# Power.net
KiCad netlist of a schematic drawn in Altium Designer
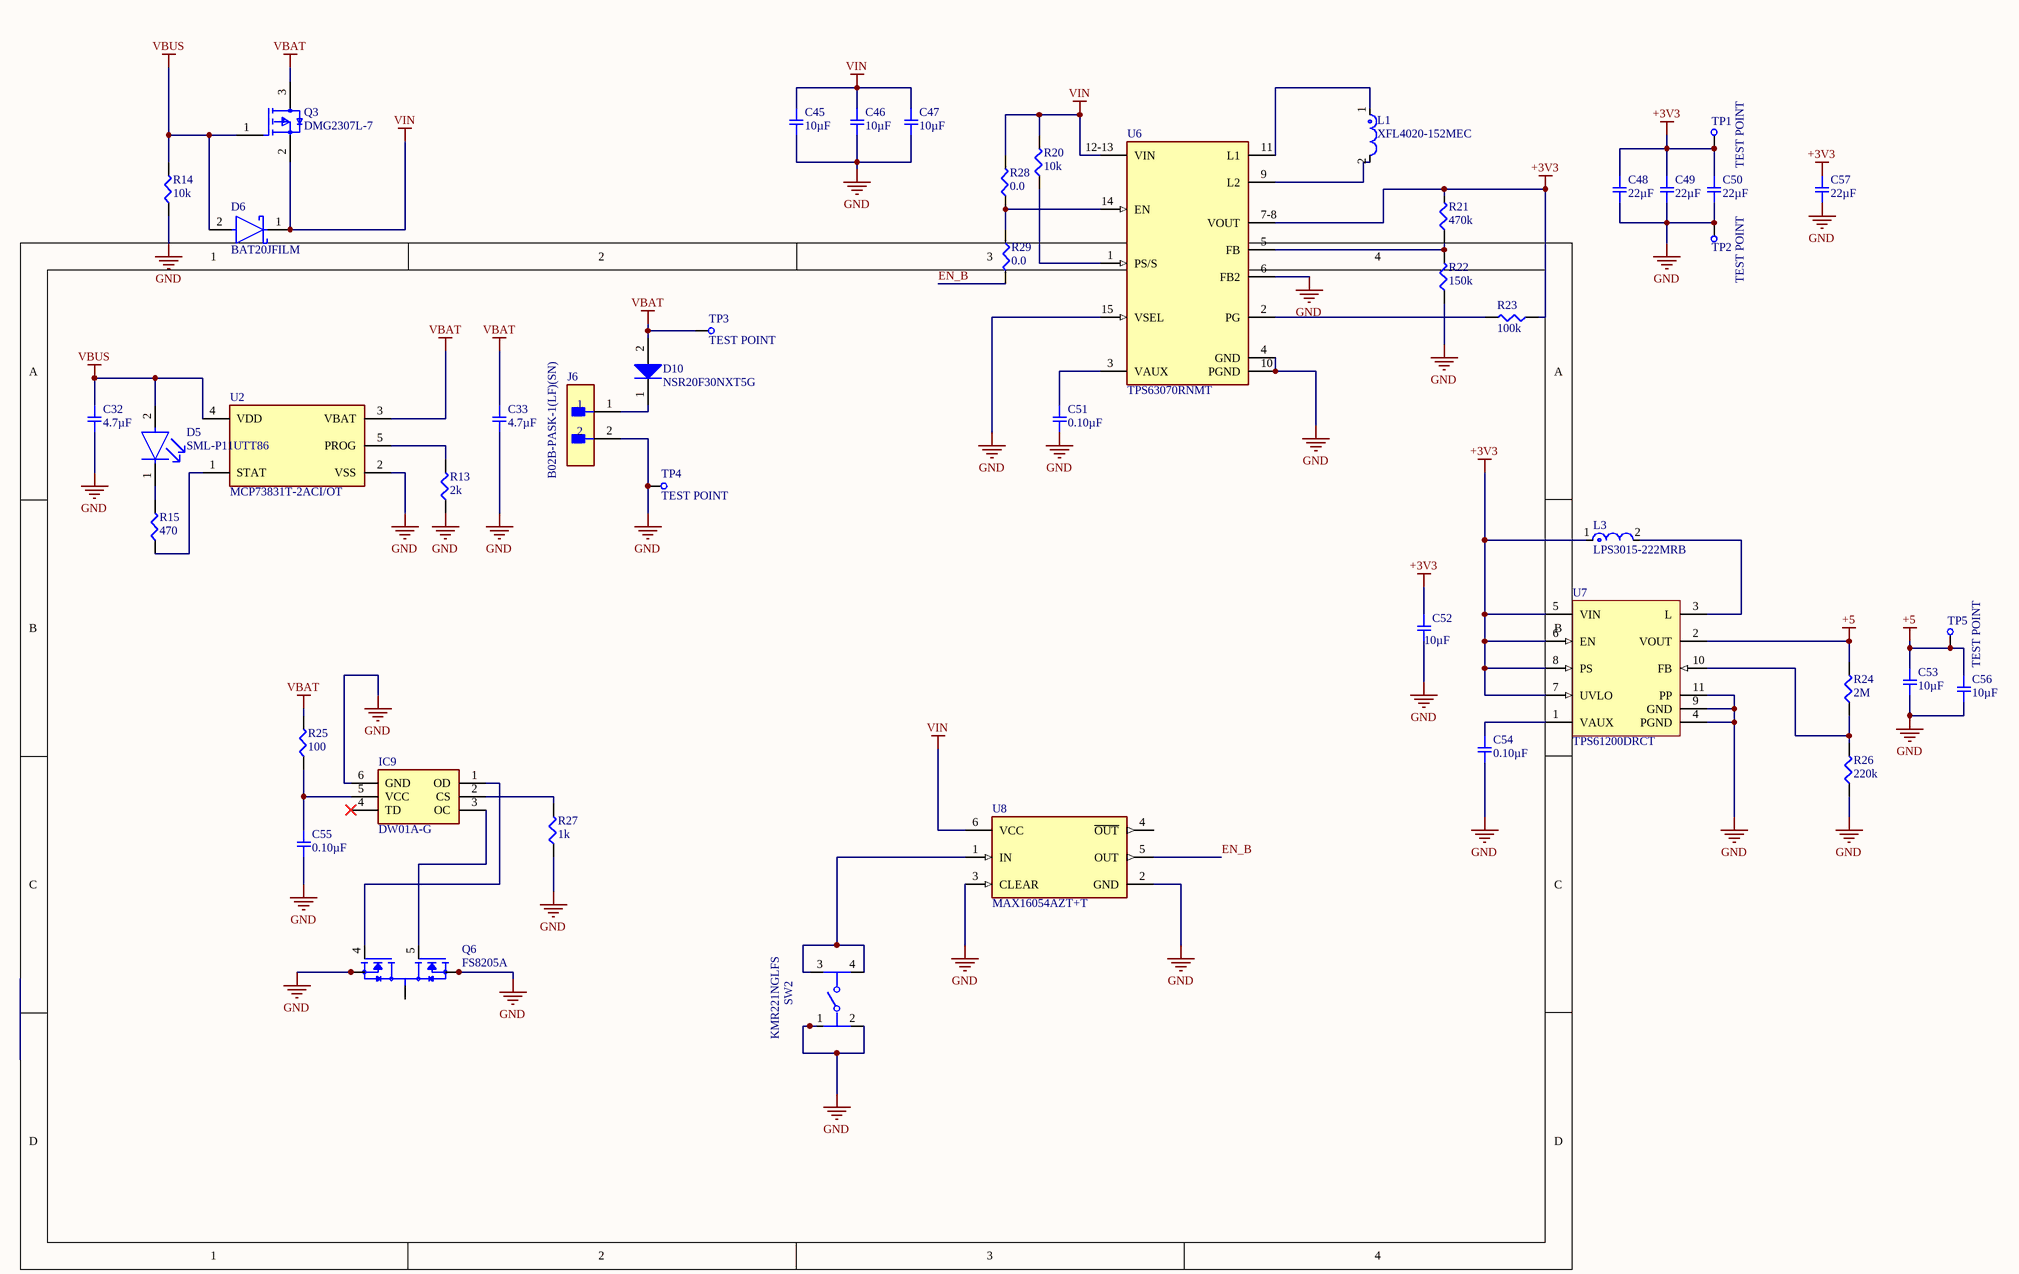
[diagram p0: Power.SchDoc]

(export (version "E")
  (design (tool "Eeschema 10.0.6"))
  (components
    (comp (ref "C32")
      (value "4.7µF")
      (footprint "SMD-0402C")
      (description "CAP CER 4.7UF 10V X5R 0402")
      (fields
        (field (name "DIGI-KEY PART NUMBER") "490-13252-1-ND")
        (field (name "PART NUMBER") "ZRB15XR61A475KE01D")
      )
      (libsource (lib "capacitor_murata_0402") (part "ZRB15XR61A475KE01D"))
    )
    (comp (ref "C33")
      (value "4.7µF")
      (footprint "SMD-0402C")
      (description "CAP CER 4.7UF 10V X5R 0402")
      (fields
        (field (name "DIGI-KEY PART NUMBER") "490-13252-1-ND")
        (field (name "PART NUMBER") "ZRB15XR61A475KE01D")
      )
      (libsource (lib "capacitor_murata_0402") (part "ZRB15XR61A475KE01D"))
    )
    (comp (ref "C45")
      (value "10µF")
      (footprint "SMD-0805C")
      (description "CAP CER 10UF 10V X7R 0805")
      (fields
        (field (name "DIGI-KEY PART NUMBER") "490-12646-1-ND")
        (field (name "PART NUMBER") "GCJ21BR71A106KE01L")
      )
      (libsource (lib "capacitor_murata_0805") (part "GCJ21BR71A106KE01L"))
    )
    (comp (ref "C46")
      (value "10µF")
      (footprint "SMD-0805C")
      (description "CAP CER 10UF 10V X7R 0805")
      (fields
        (field (name "DIGI-KEY PART NUMBER") "490-12646-1-ND")
        (field (name "PART NUMBER") "GCJ21BR71A106KE01L")
      )
      (libsource (lib "capacitor_murata_0805") (part "GCJ21BR71A106KE01L"))
    )
    (comp (ref "C47")
      (value "10µF")
      (footprint "SMD-0603C")
      (description "CAP CER 10UF 16V X6S 0603")
      (fields
        (field (name "DIGI-KEY PART NUMBER") "490-7198-1-ND")
        (field (name "PART NUMBER") "GRM188C81C106MA73D")
      )
      (libsource (lib "capacitor_murata_0603") (part "GRM188C81C106MA73D"))
    )
    (comp (ref "C48")
      (value "22µF")
      (footprint "SMD-0805C")
      (description "CAP CER 22UF 10V X5R 0805")
      (fields
        (field (name "DIGI-KEY PART NUMBER") "490-9951-1-ND")
        (field (name "PART NUMBER") "GRM219R61A226MEA0D")
      )
      (libsource (lib "capacitor_murata_0805") (part "GRM219R61A226MEA0D"))
    )
    (comp (ref "C49")
      (value "22µF")
      (footprint "SMD-0805C")
      (description "CAP CER 22UF 10V X5R 0805")
      (fields
        (field (name "DIGI-KEY PART NUMBER") "490-9951-1-ND")
        (field (name "PART NUMBER") "GRM219R61A226MEA0D")
      )
      (libsource (lib "capacitor_murata_0805") (part "GRM219R61A226MEA0D"))
    )
    (comp (ref "C50")
      (value "22µF")
      (footprint "SMD-0805C")
      (description "CAP CER 22UF 10V X5R 0805")
      (fields
        (field (name "DIGI-KEY PART NUMBER") "490-9951-1-ND")
        (field (name "PART NUMBER") "GRM219R61A226MEA0D")
      )
      (libsource (lib "capacitor_murata_0805") (part "GRM219R61A226MEA0D"))
    )
    (comp (ref "C51")
      (value "0.10µF")
      (footprint "SMD-0402C")
      (description "CAP CER 0.1UF 16V X7R 0402")
      (fields
        (field (name "DIGI-KEY PART NUMBER") "490-4759-1-ND")
        (field (name "PART NUMBER") "GCM155R71C104KA55D")
      )
      (libsource (lib "capacitor_murata_0402") (part "GCM155R71C104KA55D"))
    )
    (comp (ref "C52")
      (value "10µF")
      (footprint "SMD-0603C")
      (description "CAP CER 10UF 16V X5R 0603")
      (fields
        (field (name "DIGI-KEY PART NUMBER") "490-10729-1-ND")
        (field (name "PART NUMBER") "GRM188R61C106MAALD")
      )
      (libsource (lib "capacitor_murata_0603") (part "GRM188R61C106MAALD"))
    )
    (comp (ref "C53")
      (value "10µF")
      (footprint "SMD-0603C")
      (description "CAP CER 10UF 16V X5R 0603")
      (fields
        (field (name "DIGI-KEY PART NUMBER") "490-10729-1-ND")
        (field (name "PART NUMBER") "GRM188R61C106MAALD")
      )
      (libsource (lib "capacitor_murata_0603") (part "GRM188R61C106MAALD"))
    )
    (comp (ref "C54")
      (value "0.10µF")
      (footprint "SMD-0402C")
      (description "CAP CER 0.1UF 16V X7R 0402")
      (fields
        (field (name "DIGI-KEY PART NUMBER") "490-4759-1-ND")
        (field (name "PART NUMBER") "GCM155R71C104KA55D")
      )
      (libsource (lib "capacitor_murata_0402") (part "GCM155R71C104KA55D"))
    )
    (comp (ref "C55")
      (value "0.10µF")
      (footprint "SMD-0402C")
      (description "CAP CER 0.1UF 16V X7R 0402")
      (fields
        (field (name "DIGI-KEY PART NUMBER") "490-4759-1-ND")
        (field (name "PART NUMBER") "GCM155R71C104KA55D")
      )
      (libsource (lib "capacitor_murata_0402") (part "GCM155R71C104KA55D"))
    )
    (comp (ref "C56")
      (value "10µF")
      (footprint "SMD-0603C")
      (description "CAP CER 10UF 16V X5R 0603")
      (fields
        (field (name "DIGI-KEY PART NUMBER") "490-10729-1-ND")
        (field (name "PART NUMBER") "GRM188R61C106MAALD")
      )
      (libsource (lib "capacitor_murata_0603") (part "GRM188R61C106MAALD"))
    )
    (comp (ref "C57")
      (value "22µF")
      (footprint "SMD-0603C")
      (description "CAP CER 22UF 10V X5R 0603")
      (fields
        (field (name "DIGI-KEY PART NUMBER") "490-13243-1-ND")
        (field (name "PART NUMBER") "GRM187R61A226ME15D")
      )
      (libsource (lib "capacitor_murata_0603") (part "GRM187R61A226ME15D"))
    )
    (comp (ref "D5")
      (value "SML-P11UTT86")
      (footprint "FP-SML-P11UTT86-MFG")
      (description "LED RED CLEAR 1006 SMD")
      (libsource (lib "Altium Content Vault") (part "8706943c75ba83719d021d2fdc84c58"))
    )
    (comp (ref "D6")
      (value "BAT20JFILM")
      (footprint "FP-BAT20JFILM-MFG")
      (description "DIODE SCHOTTKY 23V 1A SOD323")
      (libsource (lib "Altium Content Vault") (part "fefb30dabb5d097ae2f038500735429"))
    )
    (comp (ref "D10")
      (value "NSR20F30NXT5G")
      (footprint "ONSC-DSN-2-512AB-01_V")
      (description "Schottky Barrier Diode, 2-Pin DSN, Pb-Free, Tape and Reel")
      (fields (field (name "MANUFACTURER") "On Semiconductor"))
      (libsource (lib "Altium Content Vault") (part "ONSC-D-K1A2-2"))
    )
    (comp (ref "IC9")
      (value "DW01A-G")
      (footprint "SamacSys:SOT95P190X145-6N")
      (description "Integrated Circuit")
      (libsource (lib "*") (part "DW01A-G"))
    )
    (comp (ref "J6")
      (value "B02B-PASK-1(LF)(SN)")
      (footprint "FP-B02B-PASK-1_LF_SN-MFG")
      (description "CONN HEADER VERT 2POS 2MM")
      (libsource (lib "Altium Content Vault") (part "3bc925449376181038e59eaffc5286c"))
    )
    (comp (ref "L1")
      (value "XFL4020-152MEC")
      (footprint "FP-XFL4020-MFG")
      (fields (field (name "TOLERANCE") "20%"))
      (libsource (lib "Altium Content Vault") (part "4cc4b267dca4c8e51f7102f422741d8"))
    )
    (comp (ref "L3")
      (value "LPS3015-222MRB")
      (footprint "FP-LPS3015-MFG")
      (description "Fixed Inductors LPS3015 AEC-Q200 2.2uH 1.4A 20% SMD")
      (fields (field (name "TOLERANCE") "20%"))
      (libsource (lib "Altium Content Vault") (part "4cc4b267dca4c8e51f7102f422741d8"))
    )
    (comp (ref "Q3")
      (value "DMG2307L-7")
      (footprint "FP-SOT23-IPC_A")
      (description "MOSFET P-CH 30V 2.5A SOT-23")
      (libsource (lib "Altium Content Vault") (part "93d33217dd9b7373daa85f78e0218cc"))
    )
    (comp (ref "Q6")
      (value "FS8205A")
      (footprint "SOP65P640X120-8N")
      (fields (field (name "MF") "Fortune Semiconductor"))
      (libsource (lib "FS8205A") (part "FS8205A"))
    )
    (comp (ref "R13")
      (value "2k")
      (footprint "SMD-0402-RES")
      (description "RES SMD 2K OHM 5% 1/10W 0402")
      (fields (field (name "PART NUMBER") "ERJ-2GEJ202X") (field (name "DIGI-KEY PART NUMBER") "P2.0KJCT-ND"))
      (libsource (lib "Panasonic_ERJ_0402") (part "ERJ-2GEJ202X"))
    )
    (comp (ref "R14")
      (value "10k")
      (footprint "SMD-0402-RES")
      (description "RES SMD 10K OHM 5% 1/10W 0402")
      (fields (field (name "PART NUMBER") "ERJ-2GEJ103X") (field (name "DIGI-KEY PART NUMBER") "P10KJCT-ND"))
      (libsource (lib "Panasonic_ERJ_0402") (part "ERJ-2GEJ103X"))
    )
    (comp (ref "R15")
      (value "470")
      (footprint "SMD-0402-RES")
      (description "RES SMD 470 OHM 1% 1/10W 0402")
      (fields (field (name "PART NUMBER") "ERJ-2RKF4700X") (field (name "DIGI-KEY PART NUMBER") "P470LCT-ND"))
      (libsource (lib "Panasonic_ERJ_0402") (part "ERJ-2RKF4700X"))
    )
    (comp (ref "R20")
      (value "10k")
      (footprint "SMD-0402-RES")
      (description "RES SMD 10K OHM 5% 1/10W 0402")
      (fields (field (name "PART NUMBER") "ERJ-2GEJ103X") (field (name "DIGI-KEY PART NUMBER") "P10KJCT-ND"))
      (libsource (lib "Panasonic_ERJ_0402") (part "ERJ-2GEJ103X"))
    )
    (comp (ref "R21")
      (value "470k")
      (footprint "SMD-0402-RES")
      (description "RES SMD 470K OHM 1% 1/10W 0402")
      (fields
        (field (name "PART NUMBER") "ERJ-2RKF4703X")
        (field (name "DIGI-KEY PART NUMBER") "P470KLCT-ND")
      )
      (libsource (lib "Panasonic_ERJ_0402") (part "ERJ-2RKF4703X"))
    )
    (comp (ref "R22")
      (value "150k")
      (footprint "SMD-0402-RES")
      (description "RES SMD 150K OHM 5% 1/10W 0402")
      (fields (field (name "PART NUMBER") "ERJ-2GEJ154X") (field (name "DIGI-KEY PART NUMBER") "P150KJCT-ND"))
      (libsource (lib "Panasonic_ERJ_0402") (part "ERJ-2GEJ154X"))
    )
    (comp (ref "R23")
      (value "100k")
      (footprint "SMD-0402-RES")
      (description "RES SMD 100K OHM 5% 1/10W 0402")
      (fields (field (name "PART NUMBER") "ERJ-2GEJ104X") (field (name "DIGI-KEY PART NUMBER") "P100KJCT-ND"))
      (libsource (lib "Panasonic_ERJ_0402") (part "ERJ-2GEJ104X"))
    )
    (comp (ref "R24")
      (value "2M")
      (footprint "SMD-0402-RES")
      (description "RES SMD 2M OHM 5% 1/10W 0402")
      (fields (field (name "PART NUMBER") "ERJ-2GEJ205X") (field (name "DIGI-KEY PART NUMBER") "P2.0MJCT-ND"))
      (libsource (lib "Panasonic_ERJ_0402") (part "ERJ-2GEJ205X"))
    )
    (comp (ref "R25")
      (value "100")
      (footprint "SMD-0402-RES")
      (description "RES SMD 100 OHM 1% 1/10W 0402")
      (fields (field (name "PART NUMBER") "ERJ-2RKF1000X") (field (name "DIGI-KEY PART NUMBER") "P100LCT-ND"))
      (libsource (lib "Panasonic_ERJ_0402") (part "ERJ-2RKF1000X"))
    )
    (comp (ref "R26")
      (value "220k")
      (footprint "SMD-0402-RES")
      (description "RES SMD 220K OHM 5% 1/10W 0402")
      (fields (field (name "PART NUMBER") "ERJ-2GEJ224X") (field (name "DIGI-KEY PART NUMBER") "P220KJCT-ND"))
      (libsource (lib "Panasonic_ERJ_0402") (part "ERJ-2GEJ224X"))
    )
    (comp (ref "R27")
      (value "1k")
      (footprint "SMD-0402-RES")
      (description "RES SMD 1K OHM 5% 1/10W 0402")
      (fields (field (name "PART NUMBER") "ERJ-2GEJ102X") (field (name "DIGI-KEY PART NUMBER") "P1.0KJCT-ND"))
      (libsource (lib "Panasonic_ERJ_0402") (part "ERJ-2GEJ102X"))
    )
    (comp (ref "R28")
      (value "0.0")
      (footprint "SMD-0402-RES")
      (description "RES SMD 0.0OHM JUMPER 1/10W 0402")
      (fields (field (name "PART NUMBER") "ERJ-2GE0R00X") (field (name "DIGI-KEY PART NUMBER") "P0.0JCT-ND"))
      (libsource (lib "Panasonic_ERJ_0402") (part "ERJ-2GE0R00X"))
    )
    (comp (ref "R29")
      (value "0.0")
      (footprint "SMD-0402-RES")
      (description "RES SMD 0.0OHM JUMPER 1/10W 0402")
      (fields (field (name "PART NUMBER") "ERJ-2GE0R00X") (field (name "DIGI-KEY PART NUMBER") "P0.0JCT-ND"))
      (libsource (lib "Panasonic_ERJ_0402") (part "ERJ-2GE0R00X"))
    )
    (comp (ref "SW2")
      (value "KMR221NGLFS")
      (footprint "FP-KMR221NGLFS-0")
      (description "SWITCH TACTILE SPST-NO 0.05A 32V")
      (fields
        (field (name "MANUFACTURER") "C&K")
        (field (name "OCTOPART") "https://octopart.com/kmr221nglfs-c%26k+components-7203802")
      )
      (libsource (lib "Altium Content Vault") (part "b8895f3f4cefb76e1819d2863dba89b"))
    )
    (comp (ref "TP1")
      (value "TEST POINT")
      (footprint "TEST POINT_30")
      (description "0.4mm hole size Test point")
      (fields (field (name "MANUFACTURER PART NUMBER") "NA"))
      (libsource (lib "ESTEEMPCBLIB") (part "TEST POINT"))
    )
    (comp (ref "TP2")
      (value "TEST POINT")
      (footprint "TEST POINT_30")
      (description "0.4mm hole size Test point")
      (fields (field (name "MANUFACTURER PART NUMBER") "NA"))
      (libsource (lib "ESTEEMPCBLIB") (part "TEST POINT"))
    )
    (comp (ref "TP3")
      (value "TEST POINT")
      (footprint "TEST POINT_30")
      (description "0.4mm hole size Test point")
      (fields (field (name "MANUFACTURER PART NUMBER") "NA"))
      (libsource (lib "ESTEEMPCBLIB") (part "TEST POINT"))
    )
    (comp (ref "TP4")
      (value "TEST POINT")
      (footprint "TEST POINT_30")
      (description "0.4mm hole size Test point")
      (fields (field (name "MANUFACTURER PART NUMBER") "NA"))
      (libsource (lib "ESTEEMPCBLIB") (part "TEST POINT"))
    )
    (comp (ref "TP5")
      (value "TEST POINT")
      (footprint "TEST POINT_30")
      (description "0.4mm hole size Test point")
      (fields (field (name "MANUFACTURER PART NUMBER") "NA"))
      (libsource (lib "ESTEEMPCBLIB") (part "TEST POINT"))
    )
    (comp (ref "U2")
      (value "MCP73831T-2ACI/OT")
      (footprint "FP-C04-091-OT-IPC_B")
      (description "IC CONTROLLR LI-ION 4.2V SOT23-5")
      (libsource (lib "Altium Content Vault") (part "61f5a3bb3429d9e0caadea342aa3b19"))
    )
    (comp (ref "U6")
      (value "TPS63070RNMT")
      (footprint "FP-RNM0015A-MFG")
      (description "IC REG BCK BST ADJ 2A 15VQFN")
      (fields
        (field (name "OCTOPART") "https://octopart.com/tps63070rnmt-texas+instruments-75117739")
        (field (name "MANUFACTURER") "Texas Instruments")
      )
      (libsource (lib "Altium Content Vault") (part "aed4bfb6dbed728ab529c70a8dd0641"))
    )
    (comp (ref "U7")
      (value "TPS61200DRCT")
      (footprint "DRC0010J_V")
      (fields (field (name "MANUFACTURER") "Texas Instruments"))
      (libsource (lib "Altium Content Vault") (part "TI-TPS61200DRC10-2400X1650TP"))
    )
    (comp (ref "U8")
      (value "MAX16054AZT+T")
      (footprint "FP-Z6-1-MFG")
      (description "IC INTFACE SPECIALIZED TSOT23-6")
      (libsource (lib "Altium Content Vault") (part "cdb3212196b4b4bbabc319418359328"))
    )
  )
  (nets
    (net (code "1") (name "+3V3") (class "Default")
      (node (ref "C48") (pin "1") (pinfunction "1_1") (pintype "passive"))
      (node (ref "C49") (pin "1") (pinfunction "1_1") (pintype "passive"))
      (node (ref "C50") (pin "1") (pinfunction "1_1") (pintype "passive"))
      (node (ref "C52") (pin "1") (pinfunction "1_1") (pintype "passive"))
      (node (ref "C57") (pin "1") (pinfunction "1_1") (pintype "passive"))
      (node (ref "L3") (pin "1") (pinfunction "1_1") (pintype "passive"))
      (node (ref "R21") (pin "2") (pinfunction "2_2") (pintype "passive"))
      (node (ref "R23") (pin "1") (pinfunction "1_1") (pintype "passive"))
      (node (ref "TP1") (pin "1") (pinfunction "1_1") (pintype "passive"))
      (node (ref "U6") (pin "7-8") (pinfunction "VOUT_7-8") (pintype "power_in"))
      (node (ref "U7") (pin "5") (pinfunction "VIN_5") (pintype "power_in"))
      (node (ref "U7") (pin "6") (pinfunction "EN_6") (pintype "input"))
      (node (ref "U7") (pin "7") (pinfunction "UVLO_7") (pintype "input"))
      (node (ref "U7") (pin "8") (pinfunction "PS_8") (pintype "input"))
    )
    (net (code "2") (name "+5") (class "Default")
      (node (ref "C53") (pin "1") (pinfunction "1_1") (pintype "passive"))
      (node (ref "C56") (pin "1") (pinfunction "1_1") (pintype "passive"))
      (node (ref "R24") (pin "2") (pinfunction "2_2") (pintype "passive"))
      (node (ref "TP5") (pin "1") (pinfunction "1_1") (pintype "passive"))
      (node (ref "U7") (pin "2") (pinfunction "VOUT_2") (pintype "power_in"))
    )
    (net (code "3") (name "/EN_B") (class "Default")
      (node (ref "R29") (pin "2") (pinfunction "2_2") (pintype "passive"))
      (node (ref "U8") (pin "5") (pinfunction "OUT_5") (pintype "output"))
    )
    (net (code "4") (name "GND") (class "Default")
      (node (ref "C32") (pin "2") (pinfunction "2_2") (pintype "passive"))
      (node (ref "C33") (pin "2") (pinfunction "2_2") (pintype "passive"))
      (node (ref "C45") (pin "2") (pinfunction "2_2") (pintype "passive"))
      (node (ref "C46") (pin "2") (pinfunction "2_2") (pintype "passive"))
      (node (ref "C47") (pin "2") (pinfunction "2_2") (pintype "passive"))
      (node (ref "C48") (pin "2") (pinfunction "2_2") (pintype "passive"))
      (node (ref "C49") (pin "2") (pinfunction "2_2") (pintype "passive"))
      (node (ref "C50") (pin "2") (pinfunction "2_2") (pintype "passive"))
      (node (ref "C51") (pin "2") (pinfunction "2_2") (pintype "passive"))
      (node (ref "C52") (pin "2") (pinfunction "2_2") (pintype "passive"))
      (node (ref "C53") (pin "2") (pinfunction "2_2") (pintype "passive"))
      (node (ref "C54") (pin "2") (pinfunction "2_2") (pintype "passive"))
      (node (ref "C55") (pin "2") (pinfunction "2_2") (pintype "passive"))
      (node (ref "C56") (pin "2") (pinfunction "2_2") (pintype "passive"))
      (node (ref "C57") (pin "2") (pinfunction "2_2") (pintype "passive"))
      (node (ref "IC9") (pin "6") (pinfunction "GND_6") (pintype "passive"))
      (node (ref "J6") (pin "2") (pinfunction "2_2") (pintype "passive"))
      (node (ref "Q6") (pin "2") (pinfunction "S1_2") (pintype "passive"))
      (node (ref "Q6") (pin "3") (pinfunction "S1_3") (pintype "passive"))
      (node (ref "Q6") (pin "6") (pinfunction "S2_6") (pintype "passive"))
      (node (ref "Q6") (pin "7") (pinfunction "S2_7") (pintype "passive"))
      (node (ref "R13") (pin "1") (pinfunction "1_1") (pintype "passive"))
      (node (ref "R14") (pin "1") (pinfunction "1_1") (pintype "passive"))
      (node (ref "R22") (pin "1") (pinfunction "1_1") (pintype "passive"))
      (node (ref "R26") (pin "1") (pinfunction "1_1") (pintype "passive"))
      (node (ref "R27") (pin "1") (pinfunction "1_1") (pintype "passive"))
      (node (ref "SW2") (pin "1") (pinfunction "1_1") (pintype "passive"))
      (node (ref "SW2") (pin "2") (pinfunction "2_2") (pintype "passive"))
      (node (ref "TP2") (pin "1") (pinfunction "1_1") (pintype "passive"))
      (node (ref "TP4") (pin "1") (pinfunction "1_1") (pintype "passive"))
      (node (ref "U2") (pin "2") (pinfunction "VSS_2") (pintype "power_in"))
      (node (ref "U6") (pin "10") (pinfunction "PGND_10") (pintype "power_in"))
      (node (ref "U6") (pin "15") (pinfunction "VSEL_15") (pintype "input"))
      (node (ref "U6") (pin "4") (pinfunction "GND_4") (pintype "power_in"))
      (node (ref "U6") (pin "6") (pinfunction "FB2_6") (pintype "passive"))
      (node (ref "U7") (pin "11") (pinfunction "PP_11") (pintype "power_in"))
      (node (ref "U7") (pin "4") (pinfunction "PGND_4") (pintype "power_in"))
      (node (ref "U7") (pin "9") (pinfunction "GND_9") (pintype "power_in"))
      (node (ref "U8") (pin "2") (pinfunction "GND_2") (pintype "power_in"))
      (node (ref "U8") (pin "3") (pinfunction "CLEAR_3") (pintype "input"))
    )
    (net (code "5") (name "Net-(D5-C)") (class "Default")
      (node (ref "D5") (pin "1") (pinfunction "C_1") (pintype "passive"))
      (node (ref "R15") (pin "2") (pinfunction "2_2") (pintype "passive"))
    )
    (net (code "6") (name "Net-(D10-K)") (class "Default")
      (node (ref "D10") (pin "1") (pinfunction "K_1") (pintype "passive"))
      (node (ref "J6") (pin "1") (pinfunction "1_1") (pintype "passive"))
    )
    (net (code "7") (name "Net-(IC9-CS)") (class "Default")
      (node (ref "IC9") (pin "2") (pinfunction "CS_2") (pintype "passive"))
      (node (ref "R27") (pin "2") (pinfunction "2_2") (pintype "passive"))
    )
    (net (code "8") (name "Net-(IC9-OC)") (class "Default")
      (node (ref "IC9") (pin "3") (pinfunction "OC_3") (pintype "passive"))
      (node (ref "Q6") (pin "5") (pinfunction "G2_5") (pintype "passive"))
    )
    (net (code "9") (name "Net-(IC9-OD)") (class "Default")
      (node (ref "IC9") (pin "1") (pinfunction "OD_1") (pintype "passive"))
      (node (ref "Q6") (pin "4") (pinfunction "G1_4") (pintype "passive"))
    )
    (net (code "10") (name "Net-(IC9-VCC)") (class "Default")
      (node (ref "C55") (pin "1") (pinfunction "1_1") (pintype "passive"))
      (node (ref "IC9") (pin "5") (pinfunction "VCC_5") (pintype "passive"))
      (node (ref "R25") (pin "1") (pinfunction "1_1") (pintype "passive"))
    )
    (net (code "11") (name "Net-(Q6-D12-Pad1)") (class "Default")
      (node (ref "Q6") (pin "1") (pinfunction "D12_1") (pintype "passive"))
      (node (ref "Q6") (pin "8") (pinfunction "D12_8") (pintype "passive"))
    )
    (net (code "12") (name "Net-(U2-PROG)") (class "Default")
      (node (ref "R13") (pin "2") (pinfunction "2_2") (pintype "passive"))
      (node (ref "U2") (pin "5") (pinfunction "PROG_5") (pintype "passive"))
    )
    (net (code "13") (name "Net-(U2-STAT)") (class "Default")
      (node (ref "R15") (pin "1") (pinfunction "1_1") (pintype "passive"))
      (node (ref "U2") (pin "1") (pinfunction "STAT_1") (pintype "passive"))
    )
    (net (code "14") (name "Net-(U6-EN)") (class "Default")
      (node (ref "R28") (pin "1") (pinfunction "1_1") (pintype "passive"))
      (node (ref "R29") (pin "1") (pinfunction "1_1") (pintype "passive"))
      (node (ref "U6") (pin "14") (pinfunction "EN_14") (pintype "input"))
    )
    (net (code "15") (name "Net-(U6-FB)") (class "Default")
      (node (ref "R21") (pin "1") (pinfunction "1_1") (pintype "passive"))
      (node (ref "R22") (pin "2") (pinfunction "2_2") (pintype "passive"))
      (node (ref "U6") (pin "5") (pinfunction "FB_5") (pintype "passive"))
    )
    (net (code "16") (name "Net-(U6-L1)") (class "Default")
      (node (ref "L1") (pin "1") (pinfunction "1_1") (pintype "passive"))
      (node (ref "U6") (pin "11") (pinfunction "L1_11") (pintype "passive"))
    )
    (net (code "17") (name "Net-(U6-L2)") (class "Default")
      (node (ref "L1") (pin "2") (pinfunction "2_2") (pintype "passive"))
      (node (ref "U6") (pin "9") (pinfunction "L2_9") (pintype "passive"))
    )
    (net (code "18") (name "Net-(U6-PG)") (class "Default")
      (node (ref "R23") (pin "2") (pinfunction "2_2") (pintype "passive"))
      (node (ref "U6") (pin "2") (pinfunction "PG_2") (pintype "open_collector"))
    )
    (net (code "19") (name "Net-(U6-PS{slash}S)") (class "Default")
      (node (ref "R20") (pin "1") (pinfunction "1_1") (pintype "passive"))
      (node (ref "U6") (pin "1") (pinfunction "PS/S_1") (pintype "input"))
    )
    (net (code "20") (name "Net-(U6-VAUX)") (class "Default")
      (node (ref "C51") (pin "1") (pinfunction "1_1") (pintype "passive"))
      (node (ref "U6") (pin "3") (pinfunction "VAUX_3") (pintype "passive"))
    )
    (net (code "21") (name "Net-(U7-FB)") (class "Default")
      (node (ref "R24") (pin "1") (pinfunction "1_1") (pintype "passive"))
      (node (ref "R26") (pin "2") (pinfunction "2_2") (pintype "passive"))
      (node (ref "U7") (pin "10") (pinfunction "FB_10") (pintype "input"))
    )
    (net (code "22") (name "Net-(U7-L)") (class "Default")
      (node (ref "L3") (pin "2") (pinfunction "2_2") (pintype "passive"))
      (node (ref "U7") (pin "3") (pinfunction "L_3") (pintype "power_in"))
    )
    (net (code "23") (name "Net-(U7-VAUX)") (class "Default")
      (node (ref "C54") (pin "1") (pinfunction "1_1") (pintype "passive"))
      (node (ref "U7") (pin "1") (pinfunction "VAUX_1") (pintype "power_in"))
    )
    (net (code "24") (name "Net-(U8-IN)") (class "Default")
      (node (ref "SW2") (pin "3") (pinfunction "3_3") (pintype "passive"))
      (node (ref "SW2") (pin "4") (pinfunction "4_4") (pintype "passive"))
      (node (ref "U8") (pin "1") (pinfunction "IN_1") (pintype "input"))
    )
    (net (code "25") (name "VBAT") (class "Default")
      (node (ref "C33") (pin "1") (pinfunction "1_1") (pintype "passive"))
      (node (ref "D10") (pin "2") (pinfunction "A_2") (pintype "passive"))
      (node (ref "Q3") (pin "3") (pinfunction "D_3") (pintype "passive"))
      (node (ref "R25") (pin "2") (pinfunction "2_2") (pintype "passive"))
      (node (ref "TP3") (pin "1") (pinfunction "1_1") (pintype "passive"))
      (node (ref "U2") (pin "3") (pinfunction "VBAT_3") (pintype "power_in"))
    )
    (net (code "26") (name "VBUS") (class "Default")
      (node (ref "C32") (pin "1") (pinfunction "1_1") (pintype "passive"))
      (node (ref "D5") (pin "2") (pinfunction "A_2") (pintype "passive"))
      (node (ref "D6") (pin "2") (pinfunction "A_2") (pintype "passive"))
      (node (ref "Q3") (pin "1") (pinfunction "G_1") (pintype "passive"))
      (node (ref "R14") (pin "2") (pinfunction "2_2") (pintype "passive"))
      (node (ref "U2") (pin "4") (pinfunction "VDD_4") (pintype "power_in"))
    )
    (net (code "27") (name "VIN") (class "Default")
      (node (ref "C45") (pin "1") (pinfunction "1_1") (pintype "passive"))
      (node (ref "C46") (pin "1") (pinfunction "1_1") (pintype "passive"))
      (node (ref "C47") (pin "1") (pinfunction "1_1") (pintype "passive"))
      (node (ref "D6") (pin "1") (pinfunction "K_1") (pintype "passive"))
      (node (ref "Q3") (pin "2") (pinfunction "S_2") (pintype "passive"))
      (node (ref "R20") (pin "2") (pinfunction "2_2") (pintype "passive"))
      (node (ref "R28") (pin "2") (pinfunction "2_2") (pintype "passive"))
      (node (ref "U6") (pin "12-13") (pinfunction "VIN_12-13") (pintype "power_in"))
      (node (ref "U8") (pin "6") (pinfunction "VCC_6") (pintype "power_in"))
    )
    (net (code "28") (name "unconnected-(IC9-TD-Pad4)") (class "Default")
      (node (ref "IC9") (pin "4") (pinfunction "TD_4") (pintype "passive+no_connect"))
    )
    (net (code "29") (name "unconnected-(U8-~{OUT}-Pad4)") (class "Default")
      (node (ref "U8") (pin "4") (pinfunction "~{OUT}_4") (pintype "output"))
    )
  )
)
